# LED_STATUS_OUTPUTS.net
KiCad netlist of a schematic drawn in Altium Designer
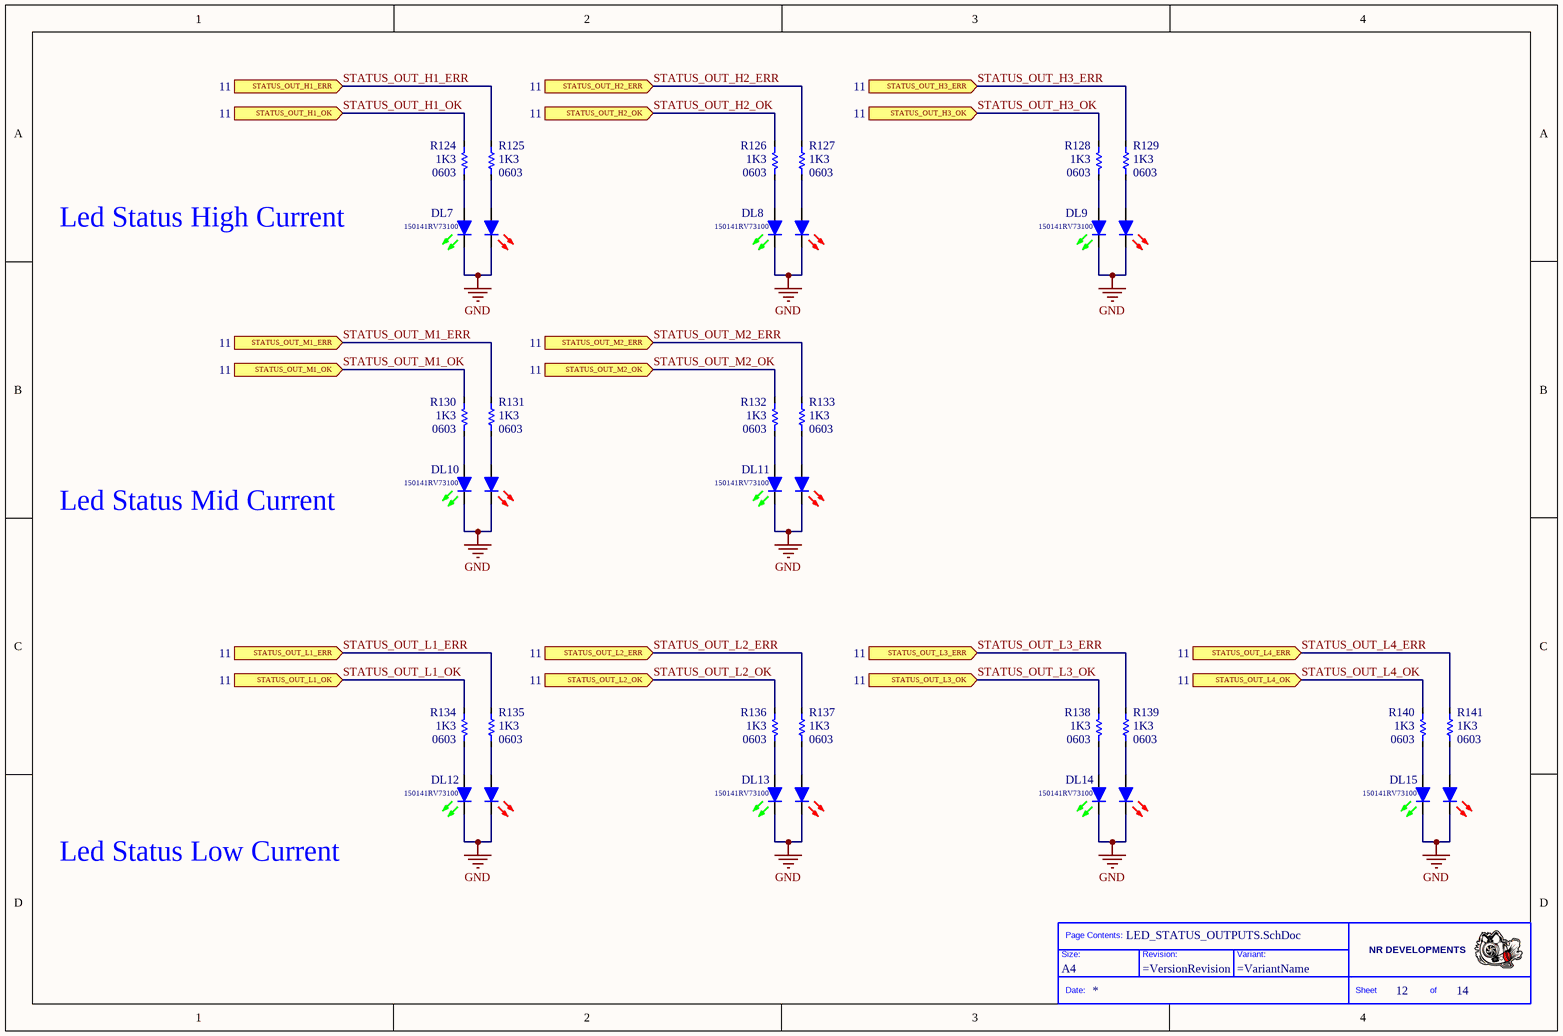
[diagram p0: LED_STATUS_OUTPUTS.SchDoc]

(export (version "E")
  (design (tool "Eeschema 10.0.6"))
  (components
    (comp (ref "DL7")
      (value "150141RV73100")
      (footprint "WURTH-SBTW_3528")
      (description "Led Red - Green 3528")
      (fields (field (name "MANUFACTURER") "Wurth") (field (name "Comment") "LED_Red_Green"))
      (libsource (lib "My_LIB") (part "LED_Red_Green"))
    )
    (comp (ref "DL8")
      (value "150141RV73100")
      (footprint "WURTH-SBTW_3528")
      (description "Led Red - Green 3528")
      (fields (field (name "MANUFACTURER") "Wurth") (field (name "Comment") "LED_Red_Green"))
      (libsource (lib "My_LIB") (part "LED_Red_Green"))
    )
    (comp (ref "DL9")
      (value "150141RV73100")
      (footprint "WURTH-SBTW_3528")
      (description "Led Red - Green 3528")
      (fields (field (name "MANUFACTURER") "Wurth") (field (name "Comment") "LED_Red_Green"))
      (libsource (lib "My_LIB") (part "LED_Red_Green"))
    )
    (comp (ref "DL10")
      (value "150141RV73100")
      (footprint "WURTH-SBTW_3528")
      (description "Led Red - Green 3528")
      (fields (field (name "MANUFACTURER") "Wurth") (field (name "Comment") "LED_Red_Green"))
      (libsource (lib "My_LIB") (part "LED_Red_Green"))
    )
    (comp (ref "DL11")
      (value "150141RV73100")
      (footprint "WURTH-SBTW_3528")
      (description "Led Red - Green 3528")
      (fields (field (name "MANUFACTURER") "Wurth") (field (name "Comment") "LED_Red_Green"))
      (libsource (lib "My_LIB") (part "LED_Red_Green"))
    )
    (comp (ref "DL12")
      (value "150141RV73100")
      (footprint "WURTH-SBTW_3528")
      (description "Led Red - Green 3528")
      (fields (field (name "MANUFACTURER") "Wurth") (field (name "Comment") "LED_Red_Green"))
      (libsource (lib "My_LIB") (part "LED_Red_Green"))
    )
    (comp (ref "DL13")
      (value "150141RV73100")
      (footprint "WURTH-SBTW_3528")
      (description "Led Red - Green 3528")
      (fields (field (name "MANUFACTURER") "Wurth") (field (name "Comment") "LED_Red_Green"))
      (libsource (lib "My_LIB") (part "LED_Red_Green"))
    )
    (comp (ref "DL14")
      (value "150141RV73100")
      (footprint "WURTH-SBTW_3528")
      (description "Led Red - Green 3528")
      (fields (field (name "MANUFACTURER") "Wurth") (field (name "Comment") "LED_Red_Green"))
      (libsource (lib "My_LIB") (part "LED_Red_Green"))
    )
    (comp (ref "DL15")
      (value "150141RV73100")
      (footprint "WURTH-SBTW_3528")
      (description "Led Red - Green 3528")
      (fields (field (name "MANUFACTURER") "Wurth") (field (name "Comment") "LED_Red_Green"))
      (libsource (lib "My_LIB") (part "LED_Red_Green"))
    )
    (comp (ref "R124")
      (value "1K3")
      (footprint "RESC1608X06M")
      (fields
        (field (name "CASE") "0603")
        (field (name "MANUFACTURER") "Vishay")
        (field (name "PARTNUMBER") "RC0603FR-071K3L")
        (field (name "Comment") "Res")
      )
      (libsource (lib "My_LIB") (part "Resistor"))
    )
    (comp (ref "R125")
      (value "1K3")
      (footprint "RESC1608X06M")
      (fields
        (field (name "CASE") "0603")
        (field (name "MANUFACTURER") "Vishay")
        (field (name "PARTNUMBER") "RC0603FR-071K3L")
        (field (name "Comment") "Res")
      )
      (libsource (lib "My_LIB") (part "Resistor"))
    )
    (comp (ref "R126")
      (value "1K3")
      (footprint "RESC1608X06M")
      (fields
        (field (name "CASE") "0603")
        (field (name "MANUFACTURER") "Vishay")
        (field (name "PARTNUMBER") "RC0603FR-071K3L")
        (field (name "Comment") "Res")
      )
      (libsource (lib "My_LIB") (part "Resistor"))
    )
    (comp (ref "R127")
      (value "1K3")
      (footprint "RESC1608X06M")
      (fields
        (field (name "CASE") "0603")
        (field (name "MANUFACTURER") "Vishay")
        (field (name "PARTNUMBER") "RC0603FR-071K3L")
        (field (name "Comment") "Res")
      )
      (libsource (lib "My_LIB") (part "Resistor"))
    )
    (comp (ref "R128")
      (value "1K3")
      (footprint "RESC1608X06M")
      (fields
        (field (name "CASE") "0603")
        (field (name "MANUFACTURER") "Vishay")
        (field (name "PARTNUMBER") "RC0603FR-071K3L")
        (field (name "Comment") "Res")
      )
      (libsource (lib "My_LIB") (part "Resistor"))
    )
    (comp (ref "R129")
      (value "1K3")
      (footprint "RESC1608X06M")
      (fields
        (field (name "CASE") "0603")
        (field (name "MANUFACTURER") "Vishay")
        (field (name "PARTNUMBER") "RC0603FR-071K3L")
        (field (name "Comment") "Res")
      )
      (libsource (lib "My_LIB") (part "Resistor"))
    )
    (comp (ref "R130")
      (value "1K3")
      (footprint "RESC1608X06M")
      (fields
        (field (name "CASE") "0603")
        (field (name "MANUFACTURER") "Vishay")
        (field (name "PARTNUMBER") "RC0603FR-071K3L")
        (field (name "Comment") "Res")
      )
      (libsource (lib "My_LIB") (part "Resistor"))
    )
    (comp (ref "R131")
      (value "1K3")
      (footprint "RESC1608X06M")
      (fields
        (field (name "CASE") "0603")
        (field (name "MANUFACTURER") "Vishay")
        (field (name "PARTNUMBER") "RC0603FR-071K3L")
        (field (name "Comment") "Res")
      )
      (libsource (lib "My_LIB") (part "Resistor"))
    )
    (comp (ref "R132")
      (value "1K3")
      (footprint "RESC1608X06M")
      (fields
        (field (name "CASE") "0603")
        (field (name "MANUFACTURER") "Vishay")
        (field (name "PARTNUMBER") "RC0603FR-071K3L")
        (field (name "Comment") "Res")
      )
      (libsource (lib "My_LIB") (part "Resistor"))
    )
    (comp (ref "R133")
      (value "1K3")
      (footprint "RESC1608X06M")
      (fields
        (field (name "CASE") "0603")
        (field (name "MANUFACTURER") "Vishay")
        (field (name "PARTNUMBER") "RC0603FR-071K3L")
        (field (name "Comment") "Res")
      )
      (libsource (lib "My_LIB") (part "Resistor"))
    )
    (comp (ref "R134")
      (value "1K3")
      (footprint "RESC1608X06M")
      (fields
        (field (name "CASE") "0603")
        (field (name "MANUFACTURER") "Vishay")
        (field (name "PARTNUMBER") "RC0603FR-071K3L")
        (field (name "Comment") "Res")
      )
      (libsource (lib "My_LIB") (part "Resistor"))
    )
    (comp (ref "R135")
      (value "1K3")
      (footprint "RESC1608X06M")
      (fields
        (field (name "CASE") "0603")
        (field (name "MANUFACTURER") "Vishay")
        (field (name "PARTNUMBER") "RC0603FR-071K3L")
        (field (name "Comment") "Res")
      )
      (libsource (lib "My_LIB") (part "Resistor"))
    )
    (comp (ref "R136")
      (value "1K3")
      (footprint "RESC1608X06M")
      (fields
        (field (name "CASE") "0603")
        (field (name "MANUFACTURER") "Vishay")
        (field (name "PARTNUMBER") "RC0603FR-071K3L")
        (field (name "Comment") "Res")
      )
      (libsource (lib "My_LIB") (part "Resistor"))
    )
    (comp (ref "R137")
      (value "1K3")
      (footprint "RESC1608X06M")
      (fields
        (field (name "CASE") "0603")
        (field (name "MANUFACTURER") "Vishay")
        (field (name "PARTNUMBER") "RC0603FR-071K3L")
        (field (name "Comment") "Res")
      )
      (libsource (lib "My_LIB") (part "Resistor"))
    )
    (comp (ref "R138")
      (value "1K3")
      (footprint "RESC1608X06M")
      (fields
        (field (name "CASE") "0603")
        (field (name "MANUFACTURER") "Vishay")
        (field (name "PARTNUMBER") "RC0603FR-071K3L")
        (field (name "Comment") "Res")
      )
      (libsource (lib "My_LIB") (part "Resistor"))
    )
    (comp (ref "R139")
      (value "1K3")
      (footprint "RESC1608X06M")
      (fields
        (field (name "CASE") "0603")
        (field (name "MANUFACTURER") "Vishay")
        (field (name "PARTNUMBER") "RC0603FR-071K3L")
        (field (name "Comment") "Res")
      )
      (libsource (lib "My_LIB") (part "Resistor"))
    )
    (comp (ref "R140")
      (value "1K3")
      (footprint "RESC1608X06M")
      (fields
        (field (name "CASE") "0603")
        (field (name "MANUFACTURER") "Vishay")
        (field (name "PARTNUMBER") "RC0603FR-071K3L")
        (field (name "Comment") "Res")
      )
      (libsource (lib "My_LIB") (part "Resistor"))
    )
    (comp (ref "R141")
      (value "1K3")
      (footprint "RESC1608X06M")
      (fields
        (field (name "CASE") "0603")
        (field (name "MANUFACTURER") "Vishay")
        (field (name "PARTNUMBER") "RC0603FR-071K3L")
        (field (name "Comment") "Res")
      )
      (libsource (lib "My_LIB") (part "Resistor"))
    )
  )
  (nets
    (net (code "1") (name "/STATUS_OUT_H1_ERR") (class "Default")
      (node (ref "R125") (pin "2") (pinfunction "2_2") (pintype "passive"))
    )
    (net (code "2") (name "/STATUS_OUT_H1_OK") (class "Default")
      (node (ref "R124") (pin "2") (pinfunction "2_2") (pintype "passive"))
    )
    (net (code "3") (name "/STATUS_OUT_H2_ERR") (class "Default")
      (node (ref "R127") (pin "2") (pinfunction "2_2") (pintype "passive"))
    )
    (net (code "4") (name "/STATUS_OUT_H2_OK") (class "Default")
      (node (ref "R126") (pin "2") (pinfunction "2_2") (pintype "passive"))
    )
    (net (code "5") (name "/STATUS_OUT_H3_ERR") (class "Default")
      (node (ref "R129") (pin "2") (pinfunction "2_2") (pintype "passive"))
    )
    (net (code "6") (name "/STATUS_OUT_H3_OK") (class "Default")
      (node (ref "R128") (pin "2") (pinfunction "2_2") (pintype "passive"))
    )
    (net (code "7") (name "/STATUS_OUT_L1_ERR") (class "Default")
      (node (ref "R135") (pin "2") (pinfunction "2_2") (pintype "passive"))
    )
    (net (code "8") (name "/STATUS_OUT_L1_OK") (class "Default")
      (node (ref "R134") (pin "2") (pinfunction "2_2") (pintype "passive"))
    )
    (net (code "9") (name "/STATUS_OUT_L2_ERR") (class "Default")
      (node (ref "R137") (pin "2") (pinfunction "2_2") (pintype "passive"))
    )
    (net (code "10") (name "/STATUS_OUT_L2_OK") (class "Default")
      (node (ref "R136") (pin "2") (pinfunction "2_2") (pintype "passive"))
    )
    (net (code "11") (name "/STATUS_OUT_L3_ERR") (class "Default")
      (node (ref "R139") (pin "2") (pinfunction "2_2") (pintype "passive"))
    )
    (net (code "12") (name "/STATUS_OUT_L3_OK") (class "Default")
      (node (ref "R138") (pin "2") (pinfunction "2_2") (pintype "passive"))
    )
    (net (code "13") (name "/STATUS_OUT_L4_ERR") (class "Default")
      (node (ref "R141") (pin "2") (pinfunction "2_2") (pintype "passive"))
    )
    (net (code "14") (name "/STATUS_OUT_L4_OK") (class "Default")
      (node (ref "R140") (pin "2") (pinfunction "2_2") (pintype "passive"))
    )
    (net (code "15") (name "/STATUS_OUT_M1_ERR") (class "Default")
      (node (ref "R131") (pin "2") (pinfunction "2_2") (pintype "passive"))
    )
    (net (code "16") (name "/STATUS_OUT_M1_OK") (class "Default")
      (node (ref "R130") (pin "2") (pinfunction "2_2") (pintype "passive"))
    )
    (net (code "17") (name "/STATUS_OUT_M2_ERR") (class "Default")
      (node (ref "R133") (pin "2") (pinfunction "2_2") (pintype "passive"))
    )
    (net (code "18") (name "/STATUS_OUT_M2_OK") (class "Default")
      (node (ref "R132") (pin "2") (pinfunction "2_2") (pintype "passive"))
    )
    (net (code "19") (name "GND") (class "Default")
      (node (ref "DL10") (pin "C1") (pinfunction "C1_C1") (pintype "passive"))
      (node (ref "DL10") (pin "C2") (pinfunction "C2_C2") (pintype "passive"))
      (node (ref "DL11") (pin "C1") (pinfunction "C1_C1") (pintype "passive"))
      (node (ref "DL11") (pin "C2") (pinfunction "C2_C2") (pintype "passive"))
      (node (ref "DL12") (pin "C1") (pinfunction "C1_C1") (pintype "passive"))
      (node (ref "DL12") (pin "C2") (pinfunction "C2_C2") (pintype "passive"))
      (node (ref "DL13") (pin "C1") (pinfunction "C1_C1") (pintype "passive"))
      (node (ref "DL13") (pin "C2") (pinfunction "C2_C2") (pintype "passive"))
      (node (ref "DL14") (pin "C1") (pinfunction "C1_C1") (pintype "passive"))
      (node (ref "DL14") (pin "C2") (pinfunction "C2_C2") (pintype "passive"))
      (node (ref "DL15") (pin "C1") (pinfunction "C1_C1") (pintype "passive"))
      (node (ref "DL15") (pin "C2") (pinfunction "C2_C2") (pintype "passive"))
      (node (ref "DL7") (pin "C1") (pinfunction "C1_C1") (pintype "passive"))
      (node (ref "DL7") (pin "C2") (pinfunction "C2_C2") (pintype "passive"))
      (node (ref "DL8") (pin "C1") (pinfunction "C1_C1") (pintype "passive"))
      (node (ref "DL8") (pin "C2") (pinfunction "C2_C2") (pintype "passive"))
      (node (ref "DL9") (pin "C1") (pinfunction "C1_C1") (pintype "passive"))
      (node (ref "DL9") (pin "C2") (pinfunction "C2_C2") (pintype "passive"))
    )
    (net (code "20") (name "Net-(DL7-PadA1)") (class "Default")
      (node (ref "DL7") (pin "A1") (pinfunction "A1_A1") (pintype "passive"))
      (node (ref "R125") (pin "1") (pinfunction "1_1") (pintype "passive"))
    )
    (net (code "21") (name "Net-(DL7-PadA2)") (class "Default")
      (node (ref "DL7") (pin "A2") (pinfunction "A2_A2") (pintype "passive"))
      (node (ref "R124") (pin "1") (pinfunction "1_1") (pintype "passive"))
    )
    (net (code "22") (name "Net-(DL8-PadA1)") (class "Default")
      (node (ref "DL8") (pin "A1") (pinfunction "A1_A1") (pintype "passive"))
      (node (ref "R127") (pin "1") (pinfunction "1_1") (pintype "passive"))
    )
    (net (code "23") (name "Net-(DL8-PadA2)") (class "Default")
      (node (ref "DL8") (pin "A2") (pinfunction "A2_A2") (pintype "passive"))
      (node (ref "R126") (pin "1") (pinfunction "1_1") (pintype "passive"))
    )
    (net (code "24") (name "Net-(DL9-PadA1)") (class "Default")
      (node (ref "DL9") (pin "A1") (pinfunction "A1_A1") (pintype "passive"))
      (node (ref "R129") (pin "1") (pinfunction "1_1") (pintype "passive"))
    )
    (net (code "25") (name "Net-(DL9-PadA2)") (class "Default")
      (node (ref "DL9") (pin "A2") (pinfunction "A2_A2") (pintype "passive"))
      (node (ref "R128") (pin "1") (pinfunction "1_1") (pintype "passive"))
    )
    (net (code "26") (name "Net-(DL10-PadA1)") (class "Default")
      (node (ref "DL10") (pin "A1") (pinfunction "A1_A1") (pintype "passive"))
      (node (ref "R131") (pin "1") (pinfunction "1_1") (pintype "passive"))
    )
    (net (code "27") (name "Net-(DL10-PadA2)") (class "Default")
      (node (ref "DL10") (pin "A2") (pinfunction "A2_A2") (pintype "passive"))
      (node (ref "R130") (pin "1") (pinfunction "1_1") (pintype "passive"))
    )
    (net (code "28") (name "Net-(DL11-PadA1)") (class "Default")
      (node (ref "DL11") (pin "A1") (pinfunction "A1_A1") (pintype "passive"))
      (node (ref "R133") (pin "1") (pinfunction "1_1") (pintype "passive"))
    )
    (net (code "29") (name "Net-(DL11-PadA2)") (class "Default")
      (node (ref "DL11") (pin "A2") (pinfunction "A2_A2") (pintype "passive"))
      (node (ref "R132") (pin "1") (pinfunction "1_1") (pintype "passive"))
    )
    (net (code "30") (name "Net-(DL12-PadA1)") (class "Default")
      (node (ref "DL12") (pin "A1") (pinfunction "A1_A1") (pintype "passive"))
      (node (ref "R135") (pin "1") (pinfunction "1_1") (pintype "passive"))
    )
    (net (code "31") (name "Net-(DL12-PadA2)") (class "Default")
      (node (ref "DL12") (pin "A2") (pinfunction "A2_A2") (pintype "passive"))
      (node (ref "R134") (pin "1") (pinfunction "1_1") (pintype "passive"))
    )
    (net (code "32") (name "Net-(DL13-PadA1)") (class "Default")
      (node (ref "DL13") (pin "A1") (pinfunction "A1_A1") (pintype "passive"))
      (node (ref "R137") (pin "1") (pinfunction "1_1") (pintype "passive"))
    )
    (net (code "33") (name "Net-(DL13-PadA2)") (class "Default")
      (node (ref "DL13") (pin "A2") (pinfunction "A2_A2") (pintype "passive"))
      (node (ref "R136") (pin "1") (pinfunction "1_1") (pintype "passive"))
    )
    (net (code "34") (name "Net-(DL14-PadA1)") (class "Default")
      (node (ref "DL14") (pin "A1") (pinfunction "A1_A1") (pintype "passive"))
      (node (ref "R139") (pin "1") (pinfunction "1_1") (pintype "passive"))
    )
    (net (code "35") (name "Net-(DL14-PadA2)") (class "Default")
      (node (ref "DL14") (pin "A2") (pinfunction "A2_A2") (pintype "passive"))
      (node (ref "R138") (pin "1") (pinfunction "1_1") (pintype "passive"))
    )
    (net (code "36") (name "Net-(DL15-PadA1)") (class "Default")
      (node (ref "DL15") (pin "A1") (pinfunction "A1_A1") (pintype "passive"))
      (node (ref "R141") (pin "1") (pinfunction "1_1") (pintype "passive"))
    )
    (net (code "37") (name "Net-(DL15-PadA2)") (class "Default")
      (node (ref "DL15") (pin "A2") (pinfunction "A2_A2") (pintype "passive"))
      (node (ref "R140") (pin "1") (pinfunction "1_1") (pintype "passive"))
    )
  )
)
